# 3_P3_Charger.net
KiCad netlist of a schematic drawn in Altium Designer
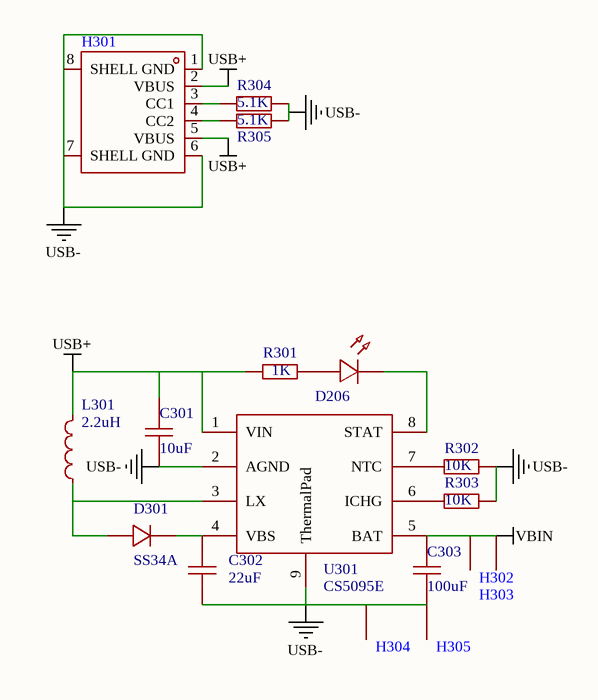
[diagram p0: 3_P3_Charger.schdoc]

(export (version "E")
  (design (tool "Eeschema 10.0.6"))
  (components
    (comp (ref "C301")
      (value "10uF")
      (footprint "C0805")
      (libsource (lib "altium-import") (part "root_3_CAP_0603_"))
    )
    (comp (ref "C302")
      (value "22uF")
      (footprint "C0805")
      (libsource (lib "altium-import") (part "root_3_CAP_0603_"))
    )
    (comp (ref "C303")
      (value "100uF")
      (footprint "C0805")
      (libsource (lib "altium-import") (part "root_3_CAP_0603_"))
    )
    (comp (ref "D206")
      (value "~")
      (footprint "LED_0603")
      (libsource (lib "altium-import") (part "root_0_LED_0603-R_"))
    )
    (comp (ref "D301")
      (value "SS34A")
      (footprint "SMA_L4.3-W2.6-LS5.2-RD")
      (fields (field (name "MANUFACTURER") "YANGJIE(扬杰)"))
      (libsource (lib "altium-import") (part "root_2_SS34A_C211775_"))
    )
    (comp (ref "H301")
      (value "~")
      (footprint "typec-31-e-11")
      (libsource (lib "altium-import") (part "root_0_mirrored_typec-31-e-11_"))
    )
    (comp (ref "H302")
      (value "~")
      (footprint "Single_Pin")
      (libsource (lib "altium-import") (part "root_3_Single_Pin_"))
    )
    (comp (ref "H303")
      (value "~")
      (footprint "Single_Pin")
      (libsource (lib "altium-import") (part "root_3_Single_Pin_"))
    )
    (comp (ref "H304")
      (value "~")
      (footprint "Single_Pin")
      (libsource (lib "altium-import") (part "root_3_Single_Pin_"))
    )
    (comp (ref "H305")
      (value "~")
      (footprint "Single_Pin")
      (libsource (lib "altium-import") (part "root_3_Single_Pin_"))
    )
    (comp (ref "L301")
      (value "2.2uH")
      (footprint "IND-SMD_L5.8-W5.2")
      (fields
        (field (name "MANUFACTURER") "Yanchuang(研创)")
        (field (name "MANUFACTURER PART") "SCCD54-4R7MT")
        (field (name "TOLERANCE") "±20%")
      )
      (libsource (lib "altium-import") (part "root_1_SCCD54-4R7MT_"))
    )
    (comp (ref "R301")
      (value "1K")
      (footprint "R0603")
      (libsource (lib "altium-import") (part "root_2_Res_0603_"))
    )
    (comp (ref "R302")
      (value "10K")
      (footprint "R0603")
      (libsource (lib "altium-import") (part "root_2_Res_0603_"))
    )
    (comp (ref "R303")
      (value "10K")
      (footprint "R0603")
      (libsource (lib "altium-import") (part "root_2_Res_0603_"))
    )
    (comp (ref "R304")
      (value "5.1K")
      (footprint "R0603")
      (libsource (lib "altium-import") (part "root_2_Res_0603_"))
    )
    (comp (ref "R305")
      (value "5.1K")
      (footprint "R0603")
      (libsource (lib "altium-import") (part "root_2_Res_0603_"))
    )
    (comp (ref "U301")
      (value "~")
      (footprint "ESOP-8_L4.9-W3.9-P1.27-LS6.0-BL-EP")
      (fields (field (name "DEVICE") "CS5095E"))
      (libsource (lib "altium-import") (part "root_0_CS5095E_"))
    )
  )
  (nets
    (net (code "1") (name "Net-(D206-A)") (class "Default")
      (node (ref "D206") (pin "2") (pinfunction "A_2") (pintype "passive"))
      (node (ref "R301") (pin "1") (pinfunction "1_1") (pintype "passive"))
    )
    (net (code "2") (name "Net-(D206-C)") (class "Default")
      (node (ref "D206") (pin "1") (pinfunction "C_1") (pintype "passive"))
      (node (ref "U301") (pin "8") (pinfunction "STAT_8") (pintype "passive"))
    )
    (net (code "3") (name "Net-(D301-A)") (class "Default")
      (node (ref "D301") (pin "2") (pinfunction "A_2") (pintype "passive"))
      (node (ref "L301") (pin "1") (pinfunction "1_1") (pintype "passive"))
      (node (ref "U301") (pin "3") (pinfunction "LX_3") (pintype "passive"))
    )
    (net (code "4") (name "Net-(D301-C)") (class "Default")
      (node (ref "C302") (pin "1") (pinfunction "1_1") (pintype "passive"))
      (node (ref "D301") (pin "1") (pinfunction "C_1") (pintype "passive"))
      (node (ref "U301") (pin "4") (pinfunction "VBS_4") (pintype "passive"))
    )
    (net (code "5") (name "Net-(H301-CC1)") (class "Default")
      (node (ref "H301") (pin "3") (pinfunction "CC1_3") (pintype "passive"))
      (node (ref "R304") (pin "2") (pinfunction "2_2") (pintype "passive"))
    )
    (net (code "6") (name "Net-(H301-CC2)") (class "Default")
      (node (ref "H301") (pin "4") (pinfunction "CC2_4") (pintype "passive"))
      (node (ref "R305") (pin "2") (pinfunction "2_2") (pintype "passive"))
    )
    (net (code "7") (name "Net-(U301-ICHG)") (class "Default")
      (node (ref "R303") (pin "2") (pinfunction "2_2") (pintype "passive"))
      (node (ref "U301") (pin "6") (pinfunction "ICHG_6") (pintype "passive"))
    )
    (net (code "8") (name "Net-(U301-NTC)") (class "Default")
      (node (ref "R302") (pin "2") (pinfunction "2_2") (pintype "passive"))
      (node (ref "U301") (pin "7") (pinfunction "NTC_7") (pintype "passive"))
    )
    (net (code "9") (name "USB+") (class "Default")
      (node (ref "C301") (pin "1") (pinfunction "1_1") (pintype "passive"))
      (node (ref "H301") (pin "2") (pinfunction "VBUS_2") (pintype "passive"))
      (node (ref "H301") (pin "5") (pinfunction "VBUS_5") (pintype "passive"))
      (node (ref "L301") (pin "2") (pinfunction "2_2") (pintype "passive"))
      (node (ref "R301") (pin "2") (pinfunction "2_2") (pintype "passive"))
      (node (ref "U301") (pin "1") (pinfunction "VIN_1") (pintype "passive"))
    )
    (net (code "10") (name "USB-") (class "Default")
      (node (ref "C301") (pin "2") (pinfunction "2_2") (pintype "passive"))
      (node (ref "C302") (pin "2") (pinfunction "2_2") (pintype "passive"))
      (node (ref "C303") (pin "2") (pinfunction "2_2") (pintype "passive"))
      (node (ref "H301") (pin "1") (pinfunction "GND_1") (pintype "passive"))
      (node (ref "H301") (pin "6") (pinfunction "GND_6") (pintype "passive"))
      (node (ref "H301") (pin "7") (pinfunction "SHELL_7") (pintype "passive"))
      (node (ref "H301") (pin "8") (pinfunction "SHELL_8") (pintype "passive"))
      (node (ref "H304") (pin "1") (pinfunction "1_1") (pintype "passive"))
      (node (ref "H305") (pin "1") (pinfunction "1_1") (pintype "passive"))
      (node (ref "R302") (pin "1") (pinfunction "1_1") (pintype "passive"))
      (node (ref "R303") (pin "1") (pinfunction "1_1") (pintype "passive"))
      (node (ref "R304") (pin "1") (pinfunction "1_1") (pintype "passive"))
      (node (ref "R305") (pin "1") (pinfunction "1_1") (pintype "passive"))
      (node (ref "U301") (pin "2") (pinfunction "AGND_2") (pintype "passive"))
      (node (ref "U301") (pin "9") (pinfunction "ThermalPad_9") (pintype "passive"))
    )
    (net (code "11") (name "VBIN") (class "Default")
      (node (ref "C303") (pin "1") (pinfunction "1_1") (pintype "passive"))
      (node (ref "H302") (pin "1") (pinfunction "1_1") (pintype "passive"))
      (node (ref "H303") (pin "1") (pinfunction "1_1") (pintype "passive"))
      (node (ref "U301") (pin "5") (pinfunction "BAT_5") (pintype "passive"))
    )
  )
)
